# Relay.net
KiCad netlist of a schematic drawn in Altium Designer
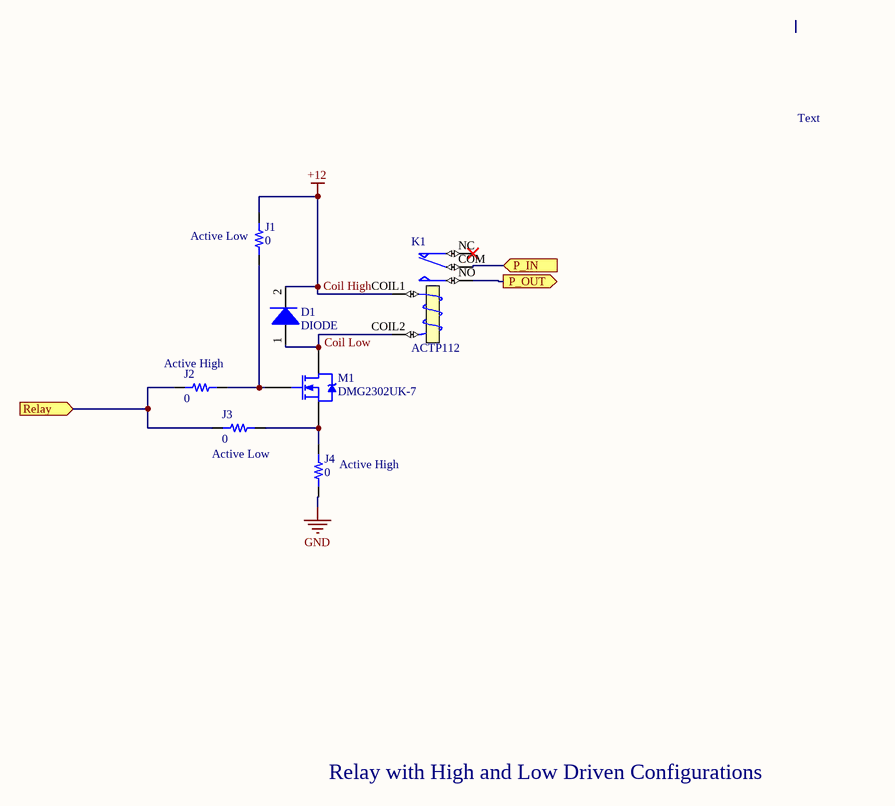
[diagram p0: Relay.SchDoc]

(export (version "E")
  (design (tool "Eeschema 10.0.6"))
  (components
    (comp (ref "D1")
      (value "DIODE")
      (footprint "SOD123F")
      (description "Diode Super Barrier 40V 1A Surface Mount SOD-123F")
      (fields (field (name "POWER") "40V") (field (name "MFRPARTNO") "1N5819HW1-7-F"))
      (libsource (lib "Altium-Lib") (part "DIODE"))
    )
    (comp (ref "J1")
      (value "0")
      (footprint "RES 0603/1608")
      (fields
        (field (name "TOLERANCE") "10%")
        (field (name "POWER") "1/10W")
        (field (name "Comment") "Resistor 1.0 0603 1/10W 10%")
        (field (name "CREATED_BY") "Nick Mah")
      )
      (libsource (lib "Altium-Lib") (part "Resistor"))
    )
    (comp (ref "J2")
      (value "0")
      (footprint "RES 0603/1608")
      (fields
        (field (name "TOLERANCE") "10%")
        (field (name "POWER") "1/10W")
        (field (name "Comment") "Resistor 1.0 0603 1/10W 10%")
        (field (name "CREATED_BY") "Nick Mah")
      )
      (libsource (lib "Altium-Lib") (part "Resistor"))
    )
    (comp (ref "J3")
      (value "0")
      (footprint "RES 0603/1608")
      (fields
        (field (name "TOLERANCE") "10%")
        (field (name "POWER") "1/10W")
        (field (name "Comment") "Resistor 1.0 0603 1/10W 10%")
        (field (name "CREATED_BY") "Nick Mah")
      )
      (libsource (lib "Altium-Lib") (part "Resistor"))
    )
    (comp (ref "J4")
      (value "0")
      (footprint "RES 0603/1608")
      (fields
        (field (name "TOLERANCE") "10%")
        (field (name "POWER") "1/10W")
        (field (name "Comment") "Resistor 1.0 0603 1/10W 10%")
        (field (name "CREATED_BY") "Nick Mah")
      )
      (libsource (lib "Altium-Lib") (part "Resistor"))
    )
    (comp (ref "K1")
      (value "ACTP112")
      (footprint "ACTP112")
      (fields (field (name "PUBLISHER") "Altium Limited"))
      (libsource (lib "Altium-Lib") (part "ACTP112"))
    )
    (comp (ref "M1")
      (value "DMG2302UK-7")
      (footprint "SOT23-3")
      (description "MOSFET N-CHANNEL 30V 5A SOT23")
      (fields (field (name "CREATED_BY") "Angel"))
      (libsource (lib "Altium-Lib") (part "DMG2302UK-7"))
    )
  )
  (nets
    (net (code "1") (name "+12") (class "Default")
      (node (ref "D1") (pin "2") (pinfunction "K_2") (pintype "passive"))
      (node (ref "J1") (pin "2") (pinfunction "2_2") (pintype "passive"))
      (node (ref "K1") (pin "COIL1") (pinfunction "T1_COIL1") (pintype "bidirectional"))
    )
    (net (code "3") (name "/P_IN") (class "Default")
      (node (ref "K1") (pin "COM") (pinfunction "COM_COM") (pintype "bidirectional"))
    )
    (net (code "4") (name "/P_OUT") (class "Default")
      (node (ref "K1") (pin "NO") (pinfunction "NO_NO") (pintype "bidirectional"))
    )
    (net (code "5") (name "/Relay") (class "Default")
      (node (ref "J2") (pin "2") (pinfunction "2_2") (pintype "passive"))
      (node (ref "J3") (pin "1") (pinfunction "1_1") (pintype "passive"))
    )
    (net (code "6") (name "GND") (class "Default")
      (node (ref "J4") (pin "2") (pinfunction "2_2") (pintype "passive"))
    )
    (net (code "7") (name "Net-(D1-A)") (class "Default")
      (node (ref "D1") (pin "1") (pinfunction "A_1") (pintype "passive"))
      (node (ref "K1") (pin "COIL2") (pinfunction "T2_COIL2") (pintype "bidirectional"))
      (node (ref "M1") (pin "3") (pinfunction "D_3") (pintype "passive"))
    )
    (net (code "8") (name "Net-(M1-G)") (class "Default")
      (node (ref "J1") (pin "1") (pinfunction "1_1") (pintype "passive"))
      (node (ref "J2") (pin "1") (pinfunction "1_1") (pintype "passive"))
      (node (ref "M1") (pin "1") (pinfunction "G_1") (pintype "passive"))
    )
    (net (code "9") (name "Net-(M1-S)") (class "Default")
      (node (ref "J3") (pin "2") (pinfunction "2_2") (pintype "passive"))
      (node (ref "J4") (pin "1") (pinfunction "1_1") (pintype "passive"))
      (node (ref "M1") (pin "2") (pinfunction "S_2") (pintype "passive"))
    )
    (net (code "10") (name "unconnected-(K1-PadNC)") (class "Default")
      (node (ref "K1") (pin "NC") (pinfunction "NC_NC") (pintype "bidirectional+no_connect"))
    )
  )
)
